# sonar_tx.net
KiCad netlist of a schematic drawn in Altium Designer
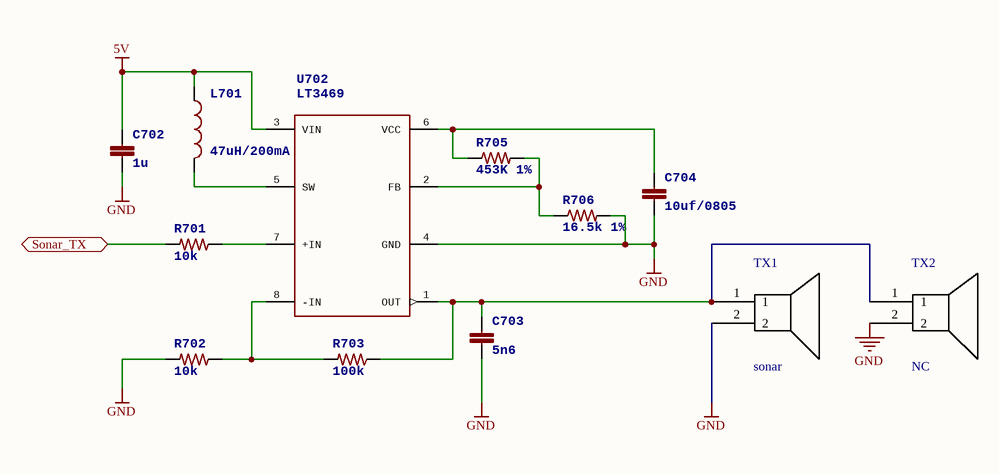
[diagram p0: sonar_tx.SchDoc]

(export (version "E")
  (design (tool "Eeschema 10.0.6"))
  (components
    (comp (ref "C702")
      (value "1u")
      (footprint "0402")
      (description "<b>Capacitor</b>\nStandard 0603 ceramic capacitor, and 0.1\" leaded capacitor.")
      (fields (field (name "PARTNO") "CC0603ZRY5V7BB105"))
      (libsource (lib "pixhawk2") (part "CAP0603"))
    )
    (comp (ref "C703")
      (value "5n6")
      (footprint "0402")
      (description "<b>Capacitor</b>\nStandard 0603 ceramic capacitor, and 0.1\" leaded capacitor.")
      (fields (field (name "PARTNO") "C0402C562K5RACTU"))
      (libsource (lib "pixhawk2") (part "CAP0402"))
    )
    (comp (ref "C704")
      (value "10uf/0805")
      (footprint "0805")
      (description "<b>Capacitor</b>\nStandard 0603 ceramic capacitor, and 0.1\" leaded capacitor.")
      (fields (field (name "PARTNO") "C1005X5R1C474K050BC"))
      (libsource (lib "pixhawk2") (part "CAP0402"))
    )
    (comp (ref "L701")
      (value "47uH/200mA")
      (footprint "L3521")
      (fields (field (name "PARTNO") "MLZ2012M470W"))
      (libsource (lib "pixhawk2") (part "INDUCTOR0805"))
    )
    (comp (ref "R701")
      (value "10k")
      (footprint "0402")
      (fields (field (name "PARTNO") "RMCF0402FT453K"))
      (libsource (lib "sonar") (part "RESISTOR0402-RES"))
    )
    (comp (ref "R702")
      (value "10k")
      (footprint "0402")
      (fields (field (name "PARTNO") "RMCF0402FT453K"))
      (libsource (lib "sonar") (part "RESISTOR0402-RES"))
    )
    (comp (ref "R703")
      (value "100k")
      (footprint "0402")
      (fields (field (name "PARTNO") "RMCF0402FT453K"))
      (libsource (lib "sonar") (part "RESISTOR0402-RES"))
    )
    (comp (ref "R705")
      (value "453K 1%")
      (footprint "0402")
      (fields (field (name "PARTNO") "RMCF0402FT453K"))
      (libsource (lib "sonar") (part "RESISTOR0402-RES"))
    )
    (comp (ref "R706")
      (value "16.5k 1%")
      (footprint "0402")
      (fields (field (name "PARTNO") "RMCF0402FT453K"))
      (libsource (lib "sonar") (part "RESISTOR0402-RES"))
    )
    (comp (ref "TX1") (value "sonar") (footprint "sonar-16mm") (libsource (lib "schlib") (part "sonar")))
    (comp (ref "TX2") (value "NC") (footprint "sonar-10mm") (libsource (lib "schlib") (part "sonar")))
    (comp (ref "U702")
      (value "LT3469")
      (footprint "SOT23-8")
      (description "LT3469 Piezo microactuator driver with boost regulator")
      (fields (field (name "PARTNO") "LT3469ETS8"))
      (libsource (lib "pixhawk2") (part "LT3469"))
    )
  )
  (nets
    (net (code "1") (name "/Sonar_TX") (class "Default")
      (node (ref "R701") (pin "2") (pinfunction "2_2") (pintype "passive"))
    )
    (net (code "2") (name "5V") (class "Default")
      (node (ref "C702") (pin "1") (pinfunction "1_1") (pintype "passive"))
      (node (ref "L701") (pin "1") (pinfunction "1_1") (pintype "passive"))
      (node (ref "U702") (pin "3") (pinfunction "VIN_3") (pintype "power_in"))
    )
    (net (code "3") (name "GND") (class "Default")
      (node (ref "C702") (pin "2") (pinfunction "2_2") (pintype "passive"))
      (node (ref "C703") (pin "2") (pinfunction "2_2") (pintype "passive"))
      (node (ref "C704") (pin "2") (pinfunction "2_2") (pintype "passive"))
      (node (ref "R702") (pin "2") (pinfunction "2_2") (pintype "passive"))
      (node (ref "R706") (pin "2") (pinfunction "2_2") (pintype "passive"))
      (node (ref "TX1") (pin "2") (pinfunction "2_2") (pintype "passive"))
      (node (ref "TX2") (pin "2") (pinfunction "2_2") (pintype "passive"))
      (node (ref "U702") (pin "4") (pinfunction "GND_4") (pintype "power_in"))
    )
    (net (code "4") (name "Net-(U702-+IN)") (class "Default")
      (node (ref "R701") (pin "1") (pinfunction "1_1") (pintype "passive"))
      (node (ref "U702") (pin "7") (pinfunction "+IN_7") (pintype "passive"))
    )
    (net (code "5") (name "Net-(U702--IN)") (class "Default")
      (node (ref "R702") (pin "1") (pinfunction "1_1") (pintype "passive"))
      (node (ref "R703") (pin "2") (pinfunction "2_2") (pintype "passive"))
      (node (ref "U702") (pin "8") (pinfunction "-IN_8") (pintype "passive"))
    )
    (net (code "6") (name "Net-(U702-FB)") (class "Default")
      (node (ref "R705") (pin "2") (pinfunction "2_2") (pintype "passive"))
      (node (ref "R706") (pin "1") (pinfunction "1_1") (pintype "passive"))
      (node (ref "U702") (pin "2") (pinfunction "FB_2") (pintype "passive"))
    )
    (net (code "7") (name "Net-(U702-OUT)") (class "Default")
      (node (ref "C703") (pin "1") (pinfunction "1_1") (pintype "passive"))
      (node (ref "R703") (pin "1") (pinfunction "1_1") (pintype "passive"))
      (node (ref "TX1") (pin "1") (pinfunction "1_1") (pintype "passive"))
      (node (ref "TX2") (pin "1") (pinfunction "1_1") (pintype "passive"))
      (node (ref "U702") (pin "1") (pinfunction "OUT_1") (pintype "output"))
    )
    (net (code "8") (name "Net-(U702-SW)") (class "Default")
      (node (ref "L701") (pin "2") (pinfunction "2_2") (pintype "passive"))
      (node (ref "U702") (pin "5") (pinfunction "SW_5") (pintype "passive"))
    )
    (net (code "9") (name "Net-(U702-VCC)") (class "Default")
      (node (ref "C704") (pin "1") (pinfunction "1_1") (pintype "passive"))
      (node (ref "R705") (pin "1") (pinfunction "1_1") (pintype "passive"))
      (node (ref "U702") (pin "6") (pinfunction "VCC_6") (pintype "passive"))
    )
  )
)
